# MPBoard_L5_Sens_2_ext.net
KiCad netlist of a schematic drawn in Altium Designer
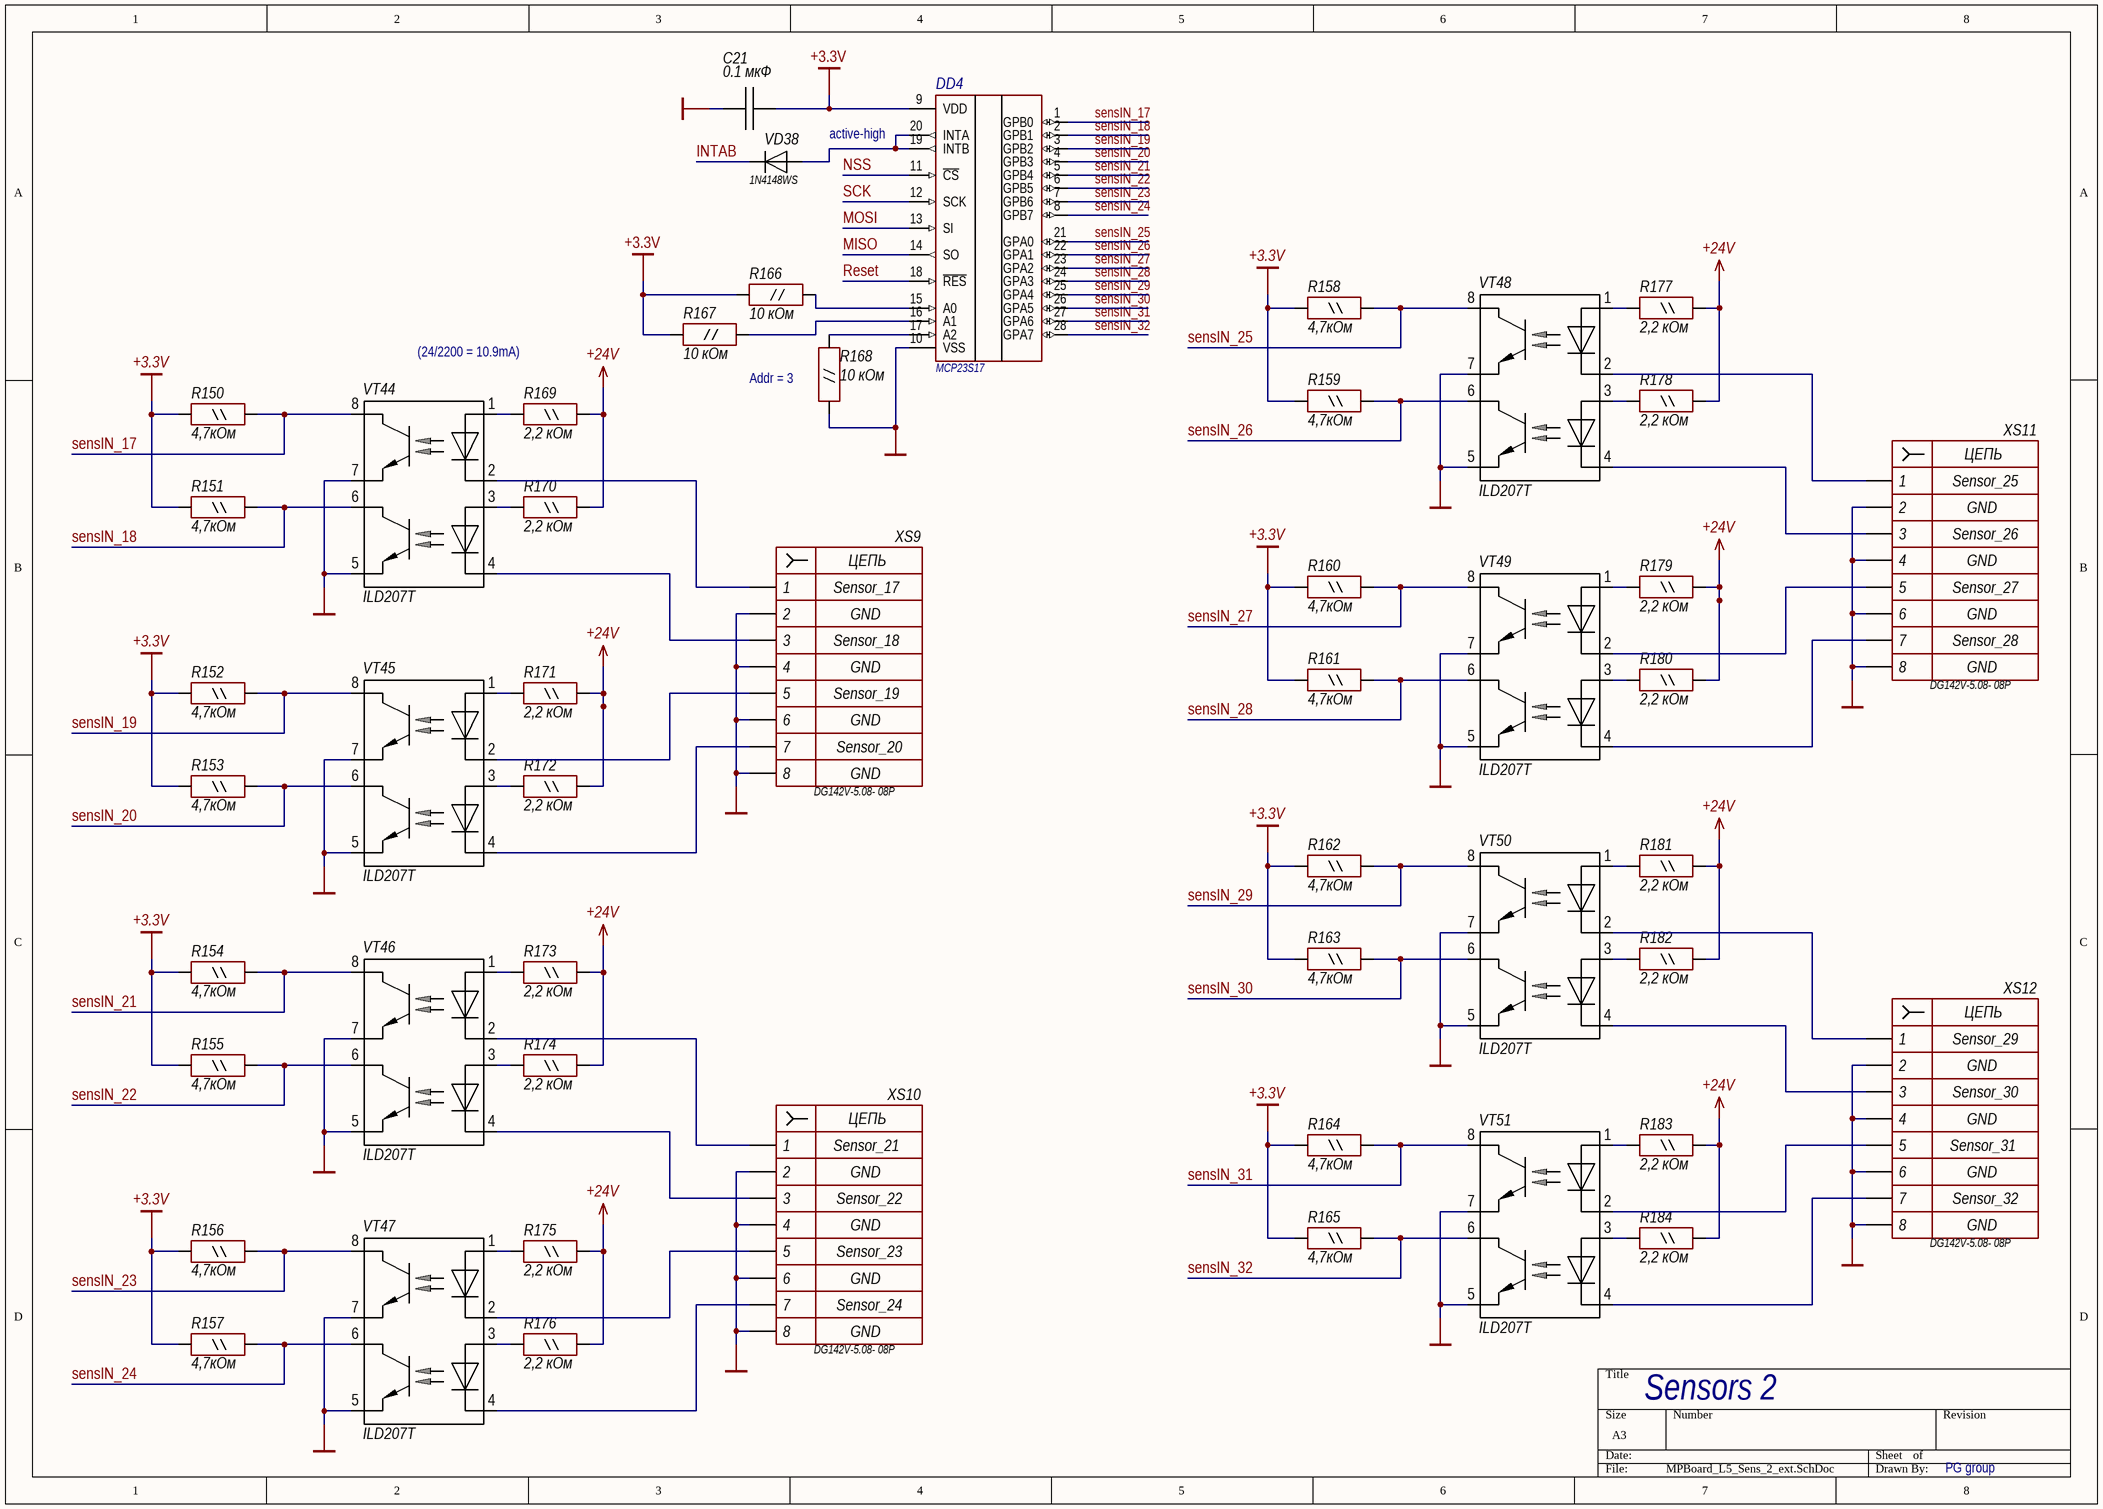
[diagram p0: MPBoard_L5_Sens_2_ext.SchDoc]

(export (version "E")
  (design (tool "Eeschema 10.0.6"))
  (components
    (comp (ref "C21")
      (value "0.1 мкФ")
      (footprint "CAP-0603")
      (description "Конденсатор")
      (fields (field (name "MF") "KEMET") (field (name "TOLERANCE") "± 10 %"))
      (libsource (lib "MainBoard") (part "C"))
    )
    (comp (ref "DD4")
      (value "MCP23S17")
      (footprint "SOIC-28")
      (description "I/O Expander 16 SPI")
      (fields (field (name "MF") "Microchip"))
      (libsource (lib "MPBoard") (part "DD_MCP23S17"))
    )
    (comp (ref "R150")
      (value "4,7кОм")
      (footprint "RES-0603")
      (description "Резистор 0.1 W")
      (fields (field (name "MF") "Vishay") (field (name "TOLERANCE") "± 1 %"))
      (libsource (lib "") (part "R_0.125W_3"))
    )
    (comp (ref "R151")
      (value "4,7кОм")
      (footprint "RES-0603")
      (description "Резистор 0.1 W")
      (fields (field (name "MF") "Vishay") (field (name "TOLERANCE") "± 1 %"))
      (libsource (lib "") (part "R_0.125W_2"))
    )
    (comp (ref "R152")
      (value "4,7кОм")
      (footprint "RES-0603")
      (description "Резистор 0.1 W")
      (fields (field (name "MF") "Vishay") (field (name "TOLERANCE") "± 1 %"))
      (libsource (lib "") (part "R_0.125W_2"))
    )
    (comp (ref "R153")
      (value "4,7кОм")
      (footprint "RES-0603")
      (description "Резистор 0.1 W")
      (fields (field (name "MF") "Vishay") (field (name "TOLERANCE") "± 1 %"))
      (libsource (lib "") (part "R_0.125W_2"))
    )
    (comp (ref "R154")
      (value "4,7кОм")
      (footprint "RES-0603")
      (description "Резистор 0.1 W")
      (fields (field (name "MF") "Vishay") (field (name "TOLERANCE") "± 1 %"))
      (libsource (lib "") (part "R_0.125W_4"))
    )
    (comp (ref "R155")
      (value "4,7кОм")
      (footprint "RES-0603")
      (description "Резистор 0.1 W")
      (fields (field (name "MF") "Vishay") (field (name "TOLERANCE") "± 1 %"))
      (libsource (lib "") (part "R_0.125W_4"))
    )
    (comp (ref "R156")
      (value "4,7кОм")
      (footprint "RES-0603")
      (description "Резистор 0.1 W")
      (fields (field (name "MF") "Vishay") (field (name "TOLERANCE") "± 1 %"))
      (libsource (lib "") (part "R_0.125W_6"))
    )
    (comp (ref "R157")
      (value "4,7кОм")
      (footprint "RES-0603")
      (description "Резистор 0.1 W")
      (fields (field (name "MF") "Vishay") (field (name "TOLERANCE") "± 1 %"))
      (libsource (lib "") (part "R_0.125W_6"))
    )
    (comp (ref "R158")
      (value "4,7кОм")
      (footprint "RES-0603")
      (description "Резистор 0.1 W")
      (fields (field (name "MF") "Vishay") (field (name "TOLERANCE") "± 1 %"))
      (libsource (lib "") (part "R_0.125W_1"))
    )
    (comp (ref "R159")
      (value "4,7кОм")
      (footprint "RES-0603")
      (description "Резистор 0.1 W")
      (fields (field (name "MF") "Vishay") (field (name "TOLERANCE") "± 1 %"))
      (libsource (lib "") (part "R_0.125W_1"))
    )
    (comp (ref "R160")
      (value "4,7кОм")
      (footprint "RES-0603")
      (description "Резистор 0.1 W")
      (fields (field (name "MF") "Vishay") (field (name "TOLERANCE") "± 1 %"))
      (libsource (lib "") (part "R_0.125W_1"))
    )
    (comp (ref "R161")
      (value "4,7кОм")
      (footprint "RES-0603")
      (description "Резистор 0.1 W")
      (fields (field (name "MF") "Vishay") (field (name "TOLERANCE") "± 1 %"))
      (libsource (lib "") (part "R_0.125W_1"))
    )
    (comp (ref "R162")
      (value "4,7кОм")
      (footprint "RES-0603")
      (description "Резистор 0.1 W")
      (fields (field (name "MF") "Vishay") (field (name "TOLERANCE") "± 1 %"))
      (libsource (lib "") (part "R_0.125W_1"))
    )
    (comp (ref "R163")
      (value "4,7кОм")
      (footprint "RES-0603")
      (description "Резистор 0.1 W")
      (fields (field (name "MF") "Vishay") (field (name "TOLERANCE") "± 1 %"))
      (libsource (lib "") (part "R_0.125W_1"))
    )
    (comp (ref "R164")
      (value "4,7кОм")
      (footprint "RES-0603")
      (description "Резистор 0.1 W")
      (fields (field (name "MF") "Vishay") (field (name "TOLERANCE") "± 1 %"))
      (libsource (lib "") (part "R_0.125W_1"))
    )
    (comp (ref "R165")
      (value "4,7кОм")
      (footprint "RES-0603")
      (description "Резистор 0.1 W")
      (fields (field (name "MF") "Vishay") (field (name "TOLERANCE") "± 1 %"))
      (libsource (lib "") (part "R_0.125W_1"))
    )
    (comp (ref "R166")
      (value "10 кОм")
      (footprint "RES-0603")
      (description "Резистор 0.1 W")
      (fields (field (name "MF") "Vishay") (field (name "TOLERANCE") "± 1 %"))
      (libsource (lib "MainBoard") (part "R_0.125W"))
    )
    (comp (ref "R167")
      (value "10 кОм")
      (footprint "RES-0603")
      (description "Резистор 0.1 W")
      (fields (field (name "MF") "Vishay") (field (name "TOLERANCE") "± 1 %"))
      (libsource (lib "MainBoard") (part "R_0.125W"))
    )
    (comp (ref "R168")
      (value "10 кОм")
      (footprint "RES-0603")
      (description "Резистор 0.1 W")
      (fields (field (name "MF") "Vishay") (field (name "TOLERANCE") "± 1 %"))
      (libsource (lib "") (part "R_0.125W_5"))
    )
    (comp (ref "R169")
      (value "2,2 кОм")
      (footprint "RES-0805")
      (description "Резистор 0.125 W")
      (fields (field (name "MF") "Vishay") (field (name "TOLERANCE") "± 1 %"))
      (libsource (lib "") (part "R_0.125W_3"))
    )
    (comp (ref "R170")
      (value "2,2 кОм")
      (footprint "RES-0805")
      (description "Резистор 0.125 W")
      (fields (field (name "MF") "Vishay") (field (name "TOLERANCE") "± 1 %"))
      (libsource (lib "") (part "R_0.125W_2"))
    )
    (comp (ref "R171")
      (value "2,2 кОм")
      (footprint "RES-0805")
      (description "Резистор 0.125 W")
      (fields (field (name "MF") "Vishay") (field (name "TOLERANCE") "± 1 %"))
      (libsource (lib "") (part "R_0.125W_2"))
    )
    (comp (ref "R172")
      (value "2,2 кОм")
      (footprint "RES-0805")
      (description "Резистор 0.125 W")
      (fields (field (name "MF") "Vishay") (field (name "TOLERANCE") "± 1 %"))
      (libsource (lib "") (part "R_0.125W_2"))
    )
    (comp (ref "R173")
      (value "2,2 кОм")
      (footprint "RES-0805")
      (description "Резистор 0.125 W")
      (fields (field (name "MF") "Vishay") (field (name "TOLERANCE") "± 1 %"))
      (libsource (lib "") (part "R_0.125W_4"))
    )
    (comp (ref "R174")
      (value "2,2 кОм")
      (footprint "RES-0805")
      (description "Резистор 0.125 W")
      (fields (field (name "MF") "Vishay") (field (name "TOLERANCE") "± 1 %"))
      (libsource (lib "") (part "R_0.125W_1"))
    )
    (comp (ref "R175")
      (value "2,2 кОм")
      (footprint "RES-0805")
      (description "Резистор 0.125 W")
      (fields (field (name "MF") "Vishay") (field (name "TOLERANCE") "± 1 %"))
      (libsource (lib "") (part "R_0.125W_6"))
    )
    (comp (ref "R176")
      (value "2,2 кОм")
      (footprint "RES-0805")
      (description "Резистор 0.125 W")
      (fields (field (name "MF") "Vishay") (field (name "TOLERANCE") "± 1 %"))
      (libsource (lib "") (part "R_0.125W_6"))
    )
    (comp (ref "R177")
      (value "2,2 кОм")
      (footprint "RES-0805")
      (description "Резистор 0.125 W")
      (fields (field (name "MF") "Vishay") (field (name "TOLERANCE") "± 1 %"))
      (libsource (lib "") (part "R_0.125W_1"))
    )
    (comp (ref "R178")
      (value "2,2 кОм")
      (footprint "RES-0805")
      (description "Резистор 0.125 W")
      (fields (field (name "MF") "Vishay") (field (name "TOLERANCE") "± 1 %"))
      (libsource (lib "") (part "R_0.125W_1"))
    )
    (comp (ref "R179")
      (value "2,2 кОм")
      (footprint "RES-0805")
      (description "Резистор 0.125 W")
      (fields (field (name "MF") "Vishay") (field (name "TOLERANCE") "± 1 %"))
      (libsource (lib "") (part "R_0.125W_1"))
    )
    (comp (ref "R180")
      (value "2,2 кОм")
      (footprint "RES-0805")
      (description "Резистор 0.125 W")
      (fields (field (name "MF") "Vishay") (field (name "TOLERANCE") "± 1 %"))
      (libsource (lib "") (part "R_0.125W_1"))
    )
    (comp (ref "R181")
      (value "2,2 кОм")
      (footprint "RES-0805")
      (description "Резистор 0.125 W")
      (fields (field (name "MF") "Vishay") (field (name "TOLERANCE") "± 1 %"))
      (libsource (lib "") (part "R_0.125W_1"))
    )
    (comp (ref "R182")
      (value "2,2 кОм")
      (footprint "RES-0805")
      (description "Резистор 0.125 W")
      (fields (field (name "MF") "Vishay") (field (name "TOLERANCE") "± 1 %"))
      (libsource (lib "") (part "R_0.125W_1"))
    )
    (comp (ref "R183")
      (value "2,2 кОм")
      (footprint "RES-0805")
      (description "Резистор 0.125 W")
      (fields (field (name "MF") "Vishay") (field (name "TOLERANCE") "± 1 %"))
      (libsource (lib "") (part "R_0.125W_1"))
    )
    (comp (ref "R184")
      (value "2,2 кОм")
      (footprint "RES-0805")
      (description "Резистор 0.125 W")
      (fields (field (name "MF") "Vishay") (field (name "TOLERANCE") "± 1 %"))
      (libsource (lib "") (part "R_0.125W_1"))
    )
    (comp (ref "VD38")
      (value "1N4148WS")
      (footprint "SOD-323")
      (description "Диод Выпрямительный")
      (fields (field (name "MF") "Diotec Semiconductor"))
      (libsource (lib "MPBoard") (part "VD"))
    )
    (comp (ref "VT44")
      (value "ILD207T")
      (footprint "SOIC-8")
      (description "Оптопара")
      (fields (field (name "MF") "Vishay"))
      (libsource (lib "MPBoard") (part "VT_2xOPTOCOUPLER"))
    )
    (comp (ref "VT45")
      (value "ILD207T")
      (footprint "SOIC-8")
      (description "Оптопара")
      (fields (field (name "MF") "Vishay"))
      (libsource (lib "MPBoard") (part "VT_2xOPTOCOUPLER"))
    )
    (comp (ref "VT46")
      (value "ILD207T")
      (footprint "SOIC-8")
      (description "Оптопара")
      (fields (field (name "MF") "Vishay"))
      (libsource (lib "MPBoard") (part "VT_2xOPTOCOUPLER"))
    )
    (comp (ref "VT47")
      (value "ILD207T")
      (footprint "SOIC-8")
      (description "Оптопара")
      (fields (field (name "MF") "Vishay"))
      (libsource (lib "MPBoard") (part "VT_2xOPTOCOUPLER"))
    )
    (comp (ref "VT48")
      (value "ILD207T")
      (footprint "SOIC-8")
      (description "Оптопара")
      (fields (field (name "MF") "Vishay"))
      (libsource (lib "MPBoard") (part "VT_2xOPTOCOUPLER"))
    )
    (comp (ref "VT49")
      (value "ILD207T")
      (footprint "SOIC-8")
      (description "Оптопара")
      (fields (field (name "MF") "Vishay"))
      (libsource (lib "MPBoard") (part "VT_2xOPTOCOUPLER"))
    )
    (comp (ref "VT50")
      (value "ILD207T")
      (footprint "SOIC-8")
      (description "Оптопара")
      (fields (field (name "MF") "Vishay"))
      (libsource (lib "MPBoard") (part "VT_2xOPTOCOUPLER"))
    )
    (comp (ref "VT51")
      (value "ILD207T")
      (footprint "SOIC-8")
      (description "Оптопара")
      (fields (field (name "MF") "Vishay"))
      (libsource (lib "MPBoard") (part "VT_2xOPTOCOUPLER"))
    )
    (comp (ref "XS9")
      (value "DG142V-5.08- 08P")
      (footprint "DG142V-5.08-08")
      (description "розетка 8 контактов")
      (fields
        (field (name "MF") "Degson Electronics")
        (field (name "MFPARTNUM") "DG142V-5.08- 08P-14-00A(H)")
        (field (name "NET6") "GND")
        (field (name "NET5") "Sensor_19")
        (field (name "NET1") "Sensor_17")
        (field (name "NET2") "GND")
        (field (name "NET3") "Sensor_18")
        (field (name "NET4") "GND")
        (field (name "NET7") "Sensor_20")
        (field (name "NET8") "GND")
      )
      (libsource (lib "") (part "XS8_2"))
    )
    (comp (ref "XS10")
      (value "DG142V-5.08- 08P")
      (footprint "DG142V-5.08-08")
      (description "розетка 8 контактов")
      (fields
        (field (name "MF") "Degson Electronics")
        (field (name "MFPARTNUM") "DG142V-5.08- 08P-14-00A(H)")
        (field (name "NET6") "GND")
        (field (name "NET5") "Sensor_23")
        (field (name "NET1") "Sensor_21")
        (field (name "NET2") "GND")
        (field (name "NET3") "Sensor_22")
        (field (name "NET4") "GND")
        (field (name "NET7") "Sensor_24")
        (field (name "NET8") "GND")
      )
      (libsource (lib "") (part "XS8_2"))
    )
    (comp (ref "XS11")
      (value "DG142V-5.08- 08P")
      (footprint "DG142V-5.08-08")
      (description "розетка 8 контактов")
      (fields
        (field (name "MF") "Degson Electronics")
        (field (name "MFPARTNUM") "DG142V-5.08- 08P-14-00A(H)")
        (field (name "NET6") "GND")
        (field (name "NET5") "Sensor_27")
        (field (name "NET1") "Sensor_25")
        (field (name "NET2") "GND")
        (field (name "NET3") "Sensor_26")
        (field (name "NET4") "GND")
        (field (name "NET7") "Sensor_28")
        (field (name "NET8") "GND")
      )
      (libsource (lib "MPBoard") (part "XS8"))
    )
    (comp (ref "XS12")
      (value "DG142V-5.08- 08P")
      (footprint "DG142V-5.08-08")
      (description "розетка 8 контактов")
      (fields
        (field (name "MF") "Degson Electronics")
        (field (name "MFPARTNUM") "DG142V-5.08- 08P-14-00A(H)")
        (field (name "NET6") "GND")
        (field (name "NET5") "Sensor_31")
        (field (name "NET1") "Sensor_29")
        (field (name "NET2") "GND")
        (field (name "NET3") "Sensor_30")
        (field (name "NET4") "GND")
        (field (name "NET7") "Sensor_32")
        (field (name "NET8") "GND")
      )
      (libsource (lib "") (part "XS8_1"))
    )
  )
  (nets
    (net (code "1") (name "+3.3V") (class "Default")
      (node (ref "C21") (pin "2") (pinfunction "2_2") (pintype "passive"))
      (node (ref "DD4") (pin "9") (pinfunction "VDD_9") (pintype "power_in"))
      (node (ref "R150") (pin "2") (pinfunction "2_2") (pintype "passive"))
      (node (ref "R151") (pin "2") (pinfunction "2_2") (pintype "passive"))
      (node (ref "R152") (pin "2") (pinfunction "2_2") (pintype "passive"))
      (node (ref "R153") (pin "2") (pinfunction "2_2") (pintype "passive"))
      (node (ref "R154") (pin "2") (pinfunction "2_2") (pintype "passive"))
      (node (ref "R155") (pin "2") (pinfunction "2_2") (pintype "passive"))
      (node (ref "R156") (pin "2") (pinfunction "2_2") (pintype "passive"))
      (node (ref "R157") (pin "2") (pinfunction "2_2") (pintype "passive"))
      (node (ref "R158") (pin "2") (pinfunction "2_2") (pintype "passive"))
      (node (ref "R159") (pin "2") (pinfunction "2_2") (pintype "passive"))
      (node (ref "R160") (pin "2") (pinfunction "2_2") (pintype "passive"))
      (node (ref "R161") (pin "2") (pinfunction "2_2") (pintype "passive"))
      (node (ref "R162") (pin "2") (pinfunction "2_2") (pintype "passive"))
      (node (ref "R163") (pin "2") (pinfunction "2_2") (pintype "passive"))
      (node (ref "R164") (pin "2") (pinfunction "2_2") (pintype "passive"))
      (node (ref "R165") (pin "2") (pinfunction "2_2") (pintype "passive"))
      (node (ref "R166") (pin "2") (pinfunction "2_2") (pintype "passive"))
      (node (ref "R167") (pin "2") (pinfunction "2_2") (pintype "passive"))
    )
    (net (code "2") (name "+24V") (class "Default")
      (node (ref "R169") (pin "1") (pinfunction "1_1") (pintype "passive"))
      (node (ref "R170") (pin "1") (pinfunction "1_1") (pintype "passive"))
      (node (ref "R171") (pin "1") (pinfunction "1_1") (pintype "passive"))
      (node (ref "R172") (pin "1") (pinfunction "1_1") (pintype "passive"))
      (node (ref "R173") (pin "1") (pinfunction "1_1") (pintype "passive"))
      (node (ref "R174") (pin "1") (pinfunction "1_1") (pintype "passive"))
      (node (ref "R175") (pin "1") (pinfunction "1_1") (pintype "passive"))
      (node (ref "R176") (pin "1") (pinfunction "1_1") (pintype "passive"))
      (node (ref "R177") (pin "1") (pinfunction "1_1") (pintype "passive"))
      (node (ref "R178") (pin "1") (pinfunction "1_1") (pintype "passive"))
      (node (ref "R179") (pin "1") (pinfunction "1_1") (pintype "passive"))
      (node (ref "R180") (pin "1") (pinfunction "1_1") (pintype "passive"))
      (node (ref "R181") (pin "1") (pinfunction "1_1") (pintype "passive"))
      (node (ref "R182") (pin "1") (pinfunction "1_1") (pintype "passive"))
      (node (ref "R183") (pin "1") (pinfunction "1_1") (pintype "passive"))
      (node (ref "R184") (pin "1") (pinfunction "1_1") (pintype "passive"))
    )
    (net (code "3") (name "/INTAB") (class "Default")
      (node (ref "VD38") (pin "2") (pinfunction "2_2") (pintype "passive"))
    )
    (net (code "4") (name "/MISO") (class "Default")
      (node (ref "DD4") (pin "14") (pinfunction "SO_14") (pintype "output"))
    )
    (net (code "5") (name "/MOSI") (class "Default")
      (node (ref "DD4") (pin "13") (pinfunction "SI_13") (pintype "input"))
    )
    (net (code "6") (name "/NSS") (class "Default")
      (node (ref "DD4") (pin "11") (pinfunction "~{CS}_11") (pintype "input"))
    )
    (net (code "7") (name "/Reset") (class "Default")
      (node (ref "DD4") (pin "18") (pinfunction "~{RES}_18") (pintype "input"))
    )
    (net (code "8") (name "/SCK") (class "Default")
      (node (ref "DD4") (pin "12") (pinfunction "SCK_12") (pintype "input"))
    )
    (net (code "9") (name "/sensIN_17") (class "Default")
      (node (ref "DD4") (pin "1") (pinfunction "GPB0_1") (pintype "bidirectional"))
      (node (ref "R150") (pin "1") (pinfunction "1_1") (pintype "passive"))
      (node (ref "VT44") (pin "8") (pintype "passive"))
    )
    (net (code "10") (name "/sensIN_18") (class "Default")
      (node (ref "DD4") (pin "2") (pinfunction "GPB1_2") (pintype "bidirectional"))
      (node (ref "R151") (pin "1") (pinfunction "1_1") (pintype "passive"))
      (node (ref "VT44") (pin "6") (pintype "passive"))
    )
    (net (code "11") (name "/sensIN_19") (class "Default")
      (node (ref "DD4") (pin "3") (pinfunction "GPB2_3") (pintype "bidirectional"))
      (node (ref "R152") (pin "1") (pinfunction "1_1") (pintype "passive"))
      (node (ref "VT45") (pin "8") (pintype "passive"))
    )
    (net (code "12") (name "/sensIN_20") (class "Default")
      (node (ref "DD4") (pin "4") (pinfunction "GPB3_4") (pintype "bidirectional"))
      (node (ref "R153") (pin "1") (pinfunction "1_1") (pintype "passive"))
      (node (ref "VT45") (pin "6") (pintype "passive"))
    )
    (net (code "13") (name "/sensIN_21") (class "Default")
      (node (ref "DD4") (pin "5") (pinfunction "GPB4_5") (pintype "bidirectional"))
      (node (ref "R154") (pin "1") (pinfunction "1_1") (pintype "passive"))
      (node (ref "VT46") (pin "8") (pintype "passive"))
    )
    (net (code "14") (name "/sensIN_22") (class "Default")
      (node (ref "DD4") (pin "6") (pinfunction "GPB5_6") (pintype "bidirectional"))
      (node (ref "R155") (pin "1") (pinfunction "1_1") (pintype "passive"))
      (node (ref "VT46") (pin "6") (pintype "passive"))
    )
    (net (code "15") (name "/sensIN_23") (class "Default")
      (node (ref "DD4") (pin "7") (pinfunction "GPB6_7") (pintype "bidirectional"))
      (node (ref "R156") (pin "1") (pinfunction "1_1") (pintype "passive"))
      (node (ref "VT47") (pin "8") (pintype "passive"))
    )
    (net (code "16") (name "/sensIN_24") (class "Default")
      (node (ref "DD4") (pin "8") (pinfunction "GPB7_8") (pintype "bidirectional"))
      (node (ref "R157") (pin "1") (pinfunction "1_1") (pintype "passive"))
      (node (ref "VT47") (pin "6") (pintype "passive"))
    )
    (net (code "17") (name "/sensIN_25") (class "Default")
      (node (ref "DD4") (pin "21") (pinfunction "GPA0_21") (pintype "bidirectional"))
      (node (ref "R158") (pin "1") (pinfunction "1_1") (pintype "passive"))
      (node (ref "VT48") (pin "8") (pintype "passive"))
    )
    (net (code "18") (name "/sensIN_26") (class "Default")
      (node (ref "DD4") (pin "22") (pinfunction "GPA1_22") (pintype "bidirectional"))
      (node (ref "R159") (pin "1") (pinfunction "1_1") (pintype "passive"))
      (node (ref "VT48") (pin "6") (pintype "passive"))
    )
    (net (code "19") (name "/sensIN_27") (class "Default")
      (node (ref "DD4") (pin "23") (pinfunction "GPA2_23") (pintype "bidirectional"))
      (node (ref "R160") (pin "1") (pinfunction "1_1") (pintype "passive"))
      (node (ref "VT49") (pin "8") (pintype "passive"))
    )
    (net (code "20") (name "/sensIN_28") (class "Default")
      (node (ref "DD4") (pin "24") (pinfunction "GPA3_24") (pintype "bidirectional"))
      (node (ref "R161") (pin "1") (pinfunction "1_1") (pintype "passive"))
      (node (ref "VT49") (pin "6") (pintype "passive"))
    )
    (net (code "21") (name "/sensIN_29") (class "Default")
      (node (ref "DD4") (pin "25") (pinfunction "GPA4_25") (pintype "bidirectional"))
      (node (ref "R162") (pin "1") (pinfunction "1_1") (pintype "passive"))
      (node (ref "VT50") (pin "8") (pintype "passive"))
    )
    (net (code "22") (name "/sensIN_30") (class "Default")
      (node (ref "DD4") (pin "26") (pinfunction "GPA5_26") (pintype "bidirectional"))
      (node (ref "R163") (pin "1") (pinfunction "1_1") (pintype "passive"))
      (node (ref "VT50") (pin "6") (pintype "passive"))
    )
    (net (code "23") (name "/sensIN_31") (class "Default")
      (node (ref "DD4") (pin "27") (pinfunction "GPA6_27") (pintype "bidirectional"))
      (node (ref "R164") (pin "1") (pinfunction "1_1") (pintype "passive"))
      (node (ref "VT51") (pin "8") (pintype "passive"))
    )
    (net (code "24") (name "/sensIN_32") (class "Default")
      (node (ref "DD4") (pin "28") (pinfunction "GPA7_28") (pintype "bidirectional"))
      (node (ref "R165") (pin "1") (pinfunction "1_1") (pintype "passive"))
      (node (ref "VT51") (pin "6") (pintype "passive"))
    )
    (net (code "25") (name "GND") (class "Default")
      (node (ref "C21") (pin "1") (pinfunction "1_1") (pintype "passive"))
      (node (ref "DD4") (pin "10") (pinfunction "VSS_10") (pintype "power_in"))
      (node (ref "R168") (pin "1") (pinfunction "1_1") (pintype "passive"))
      (node (ref "VT44") (pin "5") (pintype "passive"))
      (node (ref "VT44") (pin "7") (pintype "passive"))
      (node (ref "VT45") (pin "5") (pintype "passive"))
      (node (ref "VT45") (pin "7") (pintype "passive"))
      (node (ref "VT46") (pin "5") (pintype "passive"))
      (node (ref "VT46") (pin "7") (pintype "passive"))
      (node (ref "VT47") (pin "5") (pintype "passive"))
      (node (ref "VT47") (pin "7") (pintype "passive"))
      (node (ref "VT48") (pin "5") (pintype "passive"))
      (node (ref "VT48") (pin "7") (pintype "passive"))
      (node (ref "VT49") (pin "5") (pintype "passive"))
      (node (ref "VT49") (pin "7") (pintype "passive"))
      (node (ref "VT50") (pin "5") (pintype "passive"))
      (node (ref "VT50") (pin "7") (pintype "passive"))
      (node (ref "VT51") (pin "5") (pintype "passive"))
      (node (ref "VT51") (pin "7") (pintype "passive"))
      (node (ref "XS10") (pin "2") (pinfunction "2_2") (pintype "passive"))
      (node (ref "XS10") (pin "4") (pinfunction "4_4") (pintype "passive"))
      (node (ref "XS10") (pin "6") (pinfunction "6_6") (pintype "passive"))
      (node (ref "XS10") (pin "8") (pinfunction "8_8") (pintype "passive"))
      (node (ref "XS11") (pin "2") (pinfunction "2_2") (pintype "passive"))
      (node (ref "XS11") (pin "4") (pinfunction "4_4") (pintype "passive"))
      (node (ref "XS11") (pin "6") (pinfunction "6_6") (pintype "passive"))
      (node (ref "XS11") (pin "8") (pinfunction "8_8") (pintype "passive"))
      (node (ref "XS12") (pin "2") (pinfunction "2_2") (pintype "passive"))
      (node (ref "XS12") (pin "4") (pinfunction "4_4") (pintype "passive"))
      (node (ref "XS12") (pin "6") (pinfunction "6_6") (pintype "passive"))
      (node (ref "XS12") (pin "8") (pinfunction "8_8") (pintype "passive"))
      (node (ref "XS9") (pin "2") (pinfunction "2_2") (pintype "passive"))
      (node (ref "XS9") (pin "4") (pinfunction "4_4") (pintype "passive"))
      (node (ref "XS9") (pin "6") (pinfunction "6_6") (pintype "passive"))
      (node (ref "XS9") (pin "8") (pinfunction "8_8") (pintype "passive"))
    )
    (net (code "26") (name "Net-(DD4-A0)") (class "Default")
      (node (ref "DD4") (pin "15") (pinfunction "A0_15") (pintype "input"))
      (node (ref "R166") (pin "1") (pinfunction "1_1") (pintype "passive"))
    )
    (net (code "27") (name "Net-(DD4-A1)") (class "Default")
      (node (ref "DD4") (pin "16") (pinfunction "A1_16") (pintype "input"))
      (node (ref "R167") (pin "1") (pinfunction "1_1") (pintype "passive"))
    )
    (net (code "28") (name "Net-(DD4-A2)") (class "Default")
      (node (ref "DD4") (pin "17") (pinfunction "A2_17") (pintype "input"))
      (node (ref "R168") (pin "2") (pinfunction "2_2") (pintype "passive"))
    )
    (net (code "29") (name "Net-(DD4-INTA)") (class "Default")
      (node (ref "DD4") (pin "19") (pinfunction "INTB_19") (pintype "output"))
      (node (ref "DD4") (pin "20") (pinfunction "INTA_20") (pintype "output"))
      (node (ref "VD38") (pin "1") (pinfunction "1_1") (pintype "passive"))
    )
    (net (code "30") (name "Net-(R169-Pad2)") (class "Default")
      (node (ref "R169") (pin "2") (pinfunction "2_2") (pintype "passive"))
      (node (ref "VT44") (pin "1") (pintype "passive"))
    )
    (net (code "31") (name "Net-(R170-Pad2)") (class "Default")
      (node (ref "R170") (pin "2") (pinfunction "2_2") (pintype "passive"))
      (node (ref "VT44") (pin "3") (pintype "passive"))
    )
    (net (code "32") (name "Net-(R171-Pad2)") (class "Default")
      (node (ref "R171") (pin "2") (pinfunction "2_2") (pintype "passive"))
      (node (ref "VT45") (pin "1") (pintype "passive"))
    )
    (net (code "33") (name "Net-(R172-Pad2)") (class "Default")
      (node (ref "R172") (pin "2") (pinfunction "2_2") (pintype "passive"))
      (node (ref "VT45") (pin "3") (pintype "passive"))
    )
    (net (code "34") (name "Net-(R173-Pad2)") (class "Default")
      (node (ref "R173") (pin "2") (pinfunction "2_2") (pintype "passive"))
      (node (ref "VT46") (pin "1") (pintype "passive"))
    )
    (net (code "35") (name "Net-(R174-Pad2)") (class "Default")
      (node (ref "R174") (pin "2") (pinfunction "2_2") (pintype "passive"))
      (node (ref "VT46") (pin "3") (pintype "passive"))
    )
    (net (code "36") (name "Net-(R175-Pad2)") (class "Default")
      (node (ref "R175") (pin "2") (pinfunction "2_2") (pintype "passive"))
      (node (ref "VT47") (pin "1") (pintype "passive"))
    )
    (net (code "37") (name "Net-(R176-Pad2)") (class "Default")
      (node (ref "R176") (pin "2") (pinfunction "2_2") (pintype "passive"))
      (node (ref "VT47") (pin "3") (pintype "passive"))
    )
    (net (code "38") (name "Net-(R177-Pad2)") (class "Default")
      (node (ref "R177") (pin "2") (pinfunction "2_2") (pintype "passive"))
      (node (ref "VT48") (pin "1") (pintype "passive"))
    )
    (net (code "39") (name "Net-(R178-Pad2)") (class "Default")
      (node (ref "R178") (pin "2") (pinfunction "2_2") (pintype "passive"))
      (node (ref "VT48") (pin "3") (pintype "passive"))
    )
    (net (code "40") (name "Net-(R179-Pad2)") (class "Default")
      (node (ref "R179") (pin "2") (pinfunction "2_2") (pintype "passive"))
      (node (ref "VT49") (pin "1") (pintype "passive"))
    )
    (net (code "41") (name "Net-(R180-Pad2)") (class "Default")
      (node (ref "R180") (pin "2") (pinfunction "2_2") (pintype "passive"))
      (node (ref "VT49") (pin "3") (pintype "passive"))
    )
    (net (code "42") (name "Net-(R181-Pad2)") (class "Default")
      (node (ref "R181") (pin "2") (pinfunction "2_2") (pintype "passive"))
      (node (ref "VT50") (pin "1") (pintype "passive"))
    )
    (net (code "43") (name "Net-(R182-Pad2)") (class "Default")
      (node (ref "R182") (pin "2") (pinfunction "2_2") (pintype "passive"))
      (node (ref "VT50") (pin "3") (pintype "passive"))
    )
    (net (code "44") (name "Net-(R183-Pad2)") (class "Default")
      (node (ref "R183") (pin "2") (pinfunction "2_2") (pintype "passive"))
      (node (ref "VT51") (pin "1") (pintype "passive"))
    )
    (net (code "45") (name "Net-(R184-Pad2)") (class "Default")
      (node (ref "R184") (pin "2") (pinfunction "2_2") (pintype "passive"))
      (node (ref "VT51") (pin "3") (pintype "passive"))
    )
    (net (code "46") (name "Net-(VT44-Pad2)") (class "Default")
      (node (ref "VT44") (pin "2") (pintype "passive"))
      (node (ref "XS9") (pin "1") (pinfunction "1_1") (pintype "passive"))
    )
    (net (code "47") (name "Net-(VT44-Pad4)") (class "Default")
      (node (ref "VT44") (pin "4") (pintype "passive"))
      (node (ref "XS9") (pin "3") (pinfunction "3_3") (pintype "passive"))
    )
    (net (code "48") (name "Net-(VT45-Pad2)") (class "Default")
      (node (ref "VT45") (pin "2") (pintype "passive"))
      (node (ref "XS9") (pin "5") (pinfunction "5_5") (pintype "passive"))
    )
    (net (code "49") (name "Net-(VT45-Pad4)") (class "Default")
      (node (ref "VT45") (pin "4") (pintype "passive"))
      (node (ref "XS9") (pin "7") (pinfunction "7_7") (pintype "passive"))
    )
    (net (code "50") (name "Net-(VT46-Pad2)") (class "Default")
      (node (ref "VT46") (pin "2") (pintype "passive"))
      (node (ref "XS10") (pin "1") (pinfunction "1_1") (pintype "passive"))
    )
    (net (code "51") (name "Net-(VT46-Pad4)") (class "Default")
      (node (ref "VT46") (pin "4") (pintype "passive"))
      (node (ref "XS10") (pin "3") (pinfunction "3_3") (pintype "passive"))
    )
    (net (code "52") (name "Net-(VT47-Pad2)") (class "Default")
      (node (ref "VT47") (pin "2") (pintype "passive"))
      (node (ref "XS10") (pin "5") (pinfunction "5_5") (pintype "passive"))
    )
    (net (code "53") (name "Net-(VT47-Pad4)") (class "Default")
      (node (ref "VT47") (pin "4") (pintype "passive"))
      (node (ref "XS10") (pin "7") (pinfunction "7_7") (pintype "passive"))
    )
    (net (code "54") (name "Net-(VT48-Pad2)") (class "Default")
      (node (ref "VT48") (pin "2") (pintype "passive"))
      (node (ref "XS11") (pin "1") (pinfunction "1_1") (pintype "passive"))
    )
    (net (code "55") (name "Net-(VT48-Pad4)") (class "Default")
      (node (ref "VT48") (pin "4") (pintype "passive"))
      (node (ref "XS11") (pin "3") (pinfunction "3_3") (pintype "passive"))
    )
    (net (code "56") (name "Net-(VT49-Pad2)") (class "Default")
      (node (ref "VT49") (pin "2") (pintype "passive"))
      (node (ref "XS11") (pin "5") (pinfunction "5_5") (pintype "passive"))
    )
    (net (code "57") (name "Net-(VT49-Pad4)") (class "Default")
      (node (ref "VT49") (pin "4") (pintype "passive"))
      (node (ref "XS11") (pin "7") (pinfunction "7_7") (pintype "passive"))
    )
    (net (code "58") (name "Net-(VT50-Pad2)") (class "Default")
      (node (ref "VT50") (pin "2") (pintype "passive"))
      (node (ref "XS12") (pin "1") (pinfunction "1_1") (pintype "passive"))
    )
    (net (code "59") (name "Net-(VT50-Pad4)") (class "Default")
      (node (ref "VT50") (pin "4") (pintype "passive"))
      (node (ref "XS12") (pin "3") (pinfunction "3_3") (pintype "passive"))
    )
    (net (code "60") (name "Net-(VT51-Pad2)") (class "Default")
      (node (ref "VT51") (pin "2") (pintype "passive"))
      (node (ref "XS12") (pin "5") (pinfunction "5_5") (pintype "passive"))
    )
    (net (code "61") (name "Net-(VT51-Pad4)") (class "Default")
      (node (ref "VT51") (pin "4") (pintype "passive"))
      (node (ref "XS12") (pin "7") (pinfunction "7_7") (pintype "passive"))
    )
  )
)
